# T_STorM32_NT_motor_v42ECg4_001.net
KiCad netlist of a schematic drawn in EAGLE
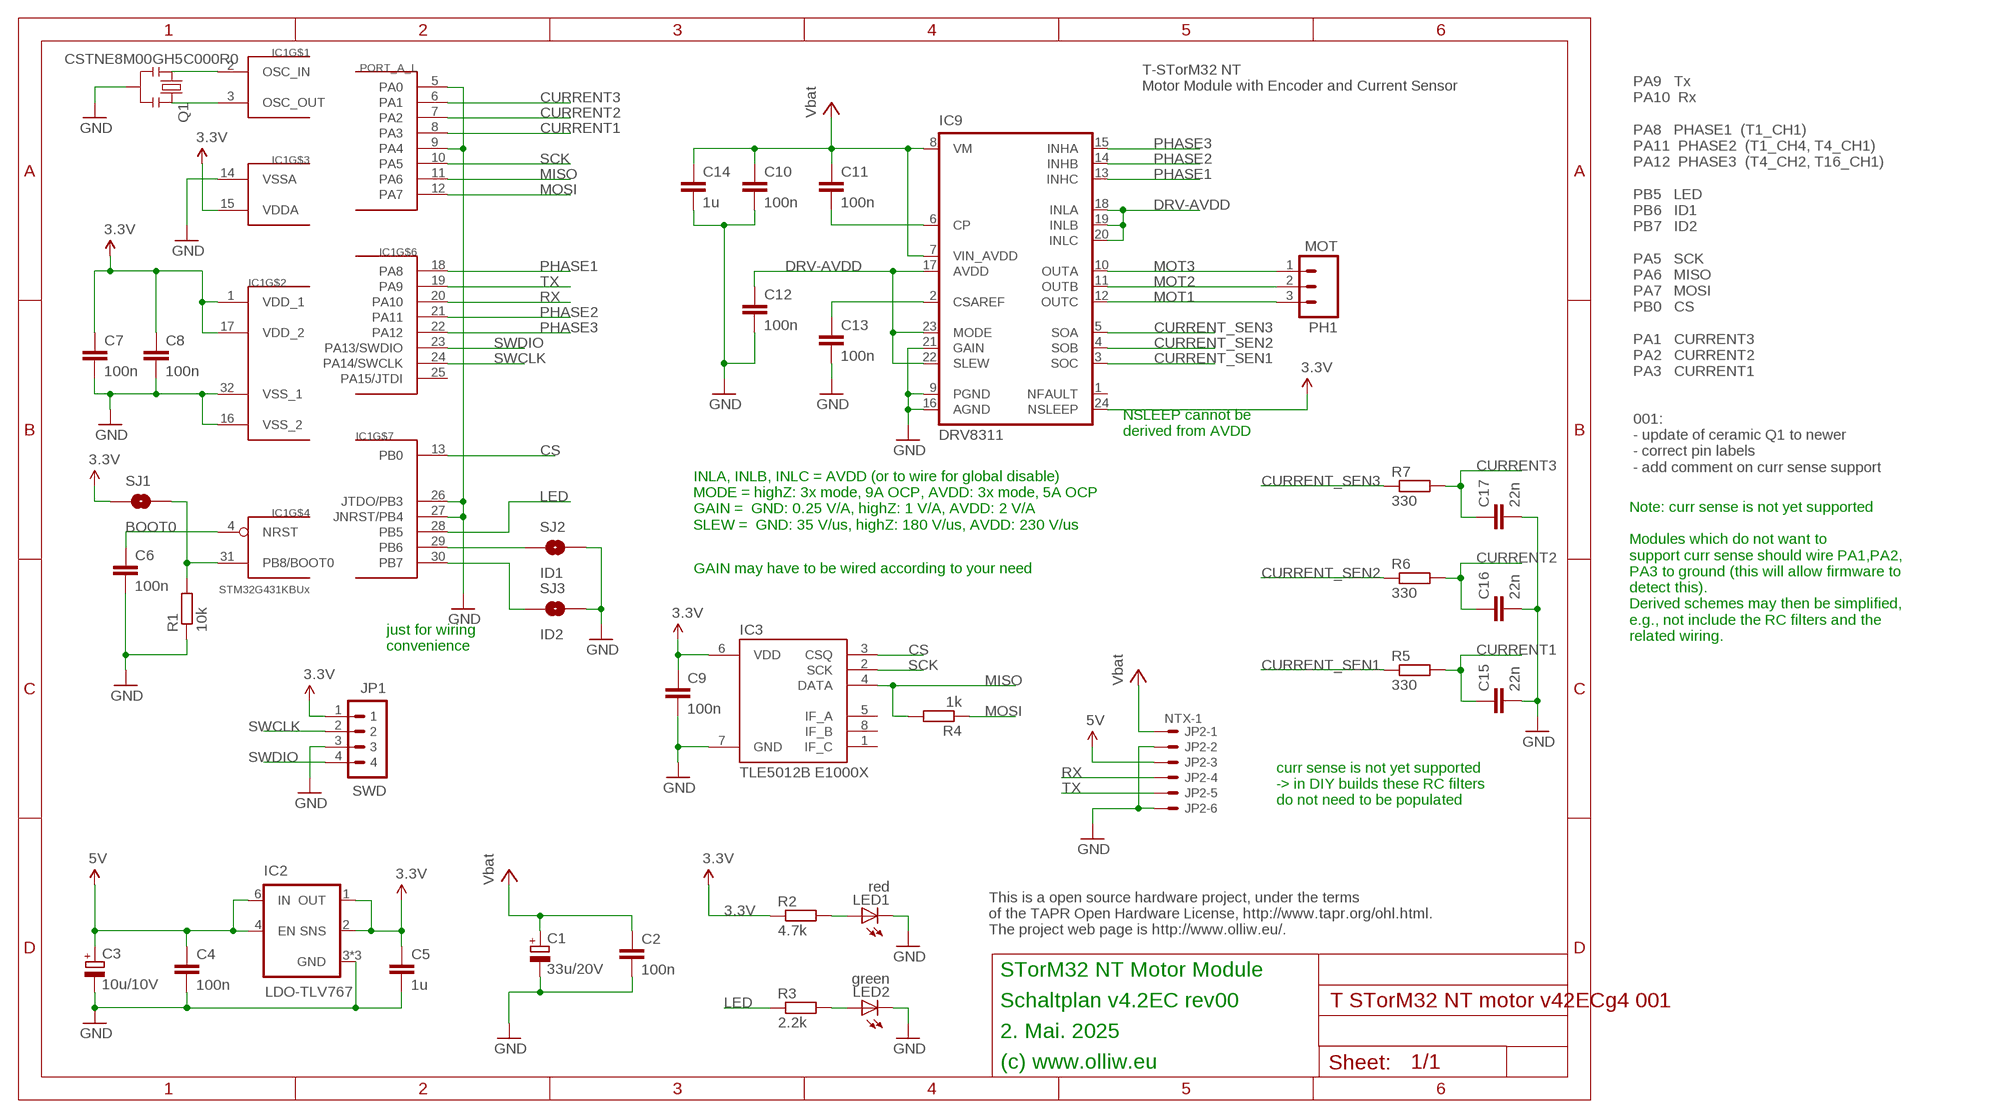
[diagram p0: schematic, sheet 1]

(export (version "E")
  (design (tool "Eeschema 10.0.6"))
  (components
    (comp (ref "C1")
      (value "33u/20V")
      (footprint "eagle-import:SMC_C")
      (libsource (lib "eagle-import") (part "CPOL-EUSMCC"))
    )
    (comp (ref "C2")
      (value "100n")
      (footprint "eagle-import:C0603")
      (libsource (lib "eagle-import") (part "C-EUC0603"))
    )
    (comp (ref "C3")
      (value "10u/10V")
      (footprint "eagle-import:SMC_B")
      (libsource (lib "eagle-import") (part "CPOL-EUSMCB"))
    )
    (comp (ref "C4")
      (value "100n")
      (footprint "eagle-import:C0603")
      (libsource (lib "eagle-import") (part "C-EUC0603"))
    )
    (comp (ref "C5")
      (value "1u")
      (footprint "eagle-import:C0603")
      (libsource (lib "eagle-import") (part "C-EUC0603"))
    )
    (comp (ref "C6")
      (value "100n")
      (footprint "eagle-import:C0402")
      (libsource (lib "eagle-import") (part "C-EUC0402"))
    )
    (comp (ref "C7")
      (value "100n")
      (footprint "eagle-import:C0402")
      (libsource (lib "eagle-import") (part "C-EUC0402"))
    )
    (comp (ref "C8")
      (value "100n")
      (footprint "eagle-import:C0402")
      (libsource (lib "eagle-import") (part "C-EUC0402"))
    )
    (comp (ref "C9")
      (value "100n")
      (footprint "eagle-import:C0402")
      (libsource (lib "eagle-import") (part "C-EUC0402"))
    )
    (comp (ref "C10")
      (value "100n")
      (footprint "eagle-import:C0402")
      (libsource (lib "eagle-import") (part "C-EUC0402"))
    )
    (comp (ref "C11")
      (value "100n")
      (footprint "eagle-import:C0402")
      (libsource (lib "eagle-import") (part "C-EUC0402"))
    )
    (comp (ref "C12")
      (value "100n")
      (footprint "eagle-import:C0402")
      (libsource (lib "eagle-import") (part "C-EUC0402"))
    )
    (comp (ref "C13")
      (value "100n")
      (footprint "eagle-import:C0402")
      (libsource (lib "eagle-import") (part "C-EUC0402"))
    )
    (comp (ref "C14")
      (value "1u")
      (footprint "eagle-import:C0603")
      (libsource (lib "eagle-import") (part "C-EUC0603"))
    )
    (comp (ref "C15")
      (value "22n")
      (footprint "eagle-import:C0402")
      (libsource (lib "eagle-import") (part "C-EUC0402"))
    )
    (comp (ref "C16")
      (value "22n")
      (footprint "eagle-import:C0402")
      (libsource (lib "eagle-import") (part "C-EUC0402"))
    )
    (comp (ref "C17")
      (value "22n")
      (footprint "eagle-import:C0402")
      (libsource (lib "eagle-import") (part "C-EUC0402"))
    )
    (comp (ref "IC1")
      (value "STM32G431KBUx")
      (footprint "eagle-import:UFQFPN32")
      (libsource (lib "eagle-import") (part "STM32G4X1KX"))
    )
    (comp (ref "IC2")
      (value "LDO-TLV767")
      (footprint "eagle-import:WSON-6-2X2")
      (libsource (lib "eagle-import") (part "LDO-TLV767"))
    )
    (comp (ref "IC3")
      (value "TLE5012B E1000X")
      (footprint "eagle-import:SO08")
      (libsource (lib "eagle-import") (part "TLE5012B"))
    )
    (comp (ref "IC9")
      (value "DRV8311")
      (footprint "eagle-import:QFN(WQFN)24-3X3-DRV8311")
      (libsource (lib "eagle-import") (part "DRV8311"))
    )
    (comp (ref "JP1")
      (value "SWD")
      (footprint "eagle-import:4X1_1P27_OCT_BILEX")
      (libsource (lib "eagle-import") (part "P4X1_1P27-OCT_BILEX"))
    )
    (comp (ref "JP2")
      (value "NTX-1")
      (footprint "eagle-import:SM06B-SRSS-TB")
      (libsource (lib "eagle-import") (part "?M06B-SRSS-TBS"))
    )
    (comp (ref "LED1")
      (value "red")
      (footprint "eagle-import:CHIPLED_0603")
      (libsource (lib "eagle-import") (part "LEDCHIPLED_0603"))
    )
    (comp (ref "LED2")
      (value "green")
      (footprint "eagle-import:CHIPLED_0603")
      (libsource (lib "eagle-import") (part "LEDCHIPLED_0603"))
    )
    (comp (ref "PH1")
      (value "MOT")
      (footprint "eagle-import:1X03_NO_SILK")
      (libsource (lib "eagle-import") (part "M031X03_NO_SILK"))
    )
    (comp (ref "Q1")
      (value "CSTNE8M00GH5C000R0")
      (footprint "eagle-import:RESONATOR-SMD")
      (libsource (lib "eagle-import") (part "RESONATORSMD"))
    )
    (comp (ref "R1")
      (value "10k")
      (footprint "eagle-import:R0402")
      (libsource (lib "eagle-import") (part "R-EU_R0402"))
    )
    (comp (ref "R2")
      (value "4.7k")
      (footprint "eagle-import:R0402")
      (libsource (lib "eagle-import") (part "R-EU_R0402"))
    )
    (comp (ref "R3")
      (value "2.2k")
      (footprint "eagle-import:R0402")
      (libsource (lib "eagle-import") (part "R-EU_R0402"))
    )
    (comp (ref "R4")
      (value "1k")
      (footprint "eagle-import:R0402")
      (libsource (lib "eagle-import") (part "R-EU_R0402"))
    )
    (comp (ref "R5")
      (value "330")
      (footprint "eagle-import:R0402")
      (libsource (lib "eagle-import") (part "R-EU_R0402"))
    )
    (comp (ref "R6")
      (value "330")
      (footprint "eagle-import:R0402")
      (libsource (lib "eagle-import") (part "R-EU_R0402"))
    )
    (comp (ref "R7")
      (value "330")
      (footprint "eagle-import:R0402")
      (libsource (lib "eagle-import") (part "R-EU_R0402"))
    )
    (comp (ref "SJ1")
      (value "BOOT0")
      (footprint "eagle-import:SJ_2S-NO")
      (libsource (lib "eagle-import") (part "SOLDERJUMPERNO"))
    )
    (comp (ref "SJ2")
      (value "ID1")
      (footprint "eagle-import:SJ_2S-NO")
      (libsource (lib "eagle-import") (part "SOLDERJUMPERNO"))
    )
    (comp (ref "SJ3")
      (value "ID2")
      (footprint "eagle-import:SJ_2S-NO")
      (libsource (lib "eagle-import") (part "SOLDERJUMPERNO"))
    )
  )
  (nets
    (net (code "1") (name "/CS") (class "Default")
      (node (ref "IC1") (pin "13") (pinfunction "PB0_13") (pintype "bidirectional"))
      (node (ref "IC3") (pin "3") (pinfunction "CSQ_3") (pintype "input"))
    )
    (net (code "2") (name "/CURRENT1") (class "Default")
      (node (ref "C15") (pin "1") (pinfunction "1_1") (pintype "passive"))
      (node (ref "IC1") (pin "8") (pinfunction "PA3_8") (pintype "bidirectional"))
      (node (ref "R5") (pin "2") (pinfunction "2_2") (pintype "passive"))
    )
    (net (code "3") (name "/CURRENT2") (class "Default")
      (node (ref "C16") (pin "1") (pinfunction "1_1") (pintype "passive"))
      (node (ref "IC1") (pin "7") (pinfunction "PA2_7") (pintype "bidirectional"))
      (node (ref "R6") (pin "2") (pinfunction "2_2") (pintype "passive"))
    )
    (net (code "4") (name "/CURRENT3") (class "Default")
      (node (ref "C17") (pin "1") (pinfunction "1_1") (pintype "passive"))
      (node (ref "IC1") (pin "6") (pinfunction "PA1_6") (pintype "bidirectional"))
      (node (ref "R7") (pin "2") (pinfunction "2_2") (pintype "passive"))
    )
    (net (code "5") (name "/CURRENT_SEN1") (class "Default")
      (node (ref "IC9") (pin "3") (pinfunction "SOC_3") (pintype "output"))
      (node (ref "R5") (pin "1") (pinfunction "1_1") (pintype "passive"))
    )
    (net (code "6") (name "/CURRENT_SEN2") (class "Default")
      (node (ref "IC9") (pin "4") (pinfunction "SOB_4") (pintype "output"))
      (node (ref "R6") (pin "1") (pinfunction "1_1") (pintype "passive"))
    )
    (net (code "7") (name "/CURRENT_SEN3") (class "Default")
      (node (ref "IC9") (pin "5") (pinfunction "SOA_5") (pintype "output"))
      (node (ref "R7") (pin "1") (pinfunction "1_1") (pintype "passive"))
    )
    (net (code "8") (name "/DRV-AVDD") (class "Default")
      (node (ref "C12") (pin "1") (pinfunction "1_1") (pintype "passive"))
      (node (ref "IC9") (pin "17") (pinfunction "AVDD_17") (pintype "power_in"))
      (node (ref "IC9") (pin "18") (pinfunction "INLA_18") (pintype "input"))
      (node (ref "IC9") (pin "19") (pinfunction "INLB_19") (pintype "input"))
      (node (ref "IC9") (pin "20") (pinfunction "INLC_20") (pintype "input"))
      (node (ref "IC9") (pin "22") (pinfunction "SLEW_22") (pintype "input"))
      (node (ref "IC9") (pin "23") (pinfunction "MODE_23") (pintype "input"))
    )
    (net (code "9") (name "/LED") (class "Default")
      (node (ref "IC1") (pin "28") (pinfunction "PB5_28") (pintype "bidirectional"))
      (node (ref "R3") (pin "1") (pinfunction "1_1") (pintype "passive"))
    )
    (net (code "10") (name "/MISO") (class "Default")
      (node (ref "IC1") (pin "11") (pinfunction "PA6_11") (pintype "bidirectional"))
      (node (ref "IC3") (pin "4") (pinfunction "DATA_4") (pintype "bidirectional"))
      (node (ref "R4") (pin "2") (pinfunction "2_2") (pintype "passive"))
    )
    (net (code "11") (name "/MOSI") (class "Default")
      (node (ref "IC1") (pin "12") (pinfunction "PA7_12") (pintype "bidirectional"))
      (node (ref "R4") (pin "1") (pinfunction "1_1") (pintype "passive"))
    )
    (net (code "12") (name "/MOT1") (class "Default")
      (node (ref "IC9") (pin "12") (pinfunction "OUTC_12") (pintype "output"))
      (node (ref "PH1") (pin "3") (pinfunction "3_3") (pintype "passive"))
    )
    (net (code "13") (name "/MOT2") (class "Default")
      (node (ref "IC9") (pin "11") (pinfunction "OUTB_11") (pintype "output"))
      (node (ref "PH1") (pin "2") (pinfunction "2_2") (pintype "passive"))
    )
    (net (code "14") (name "/MOT3") (class "Default")
      (node (ref "IC9") (pin "10") (pinfunction "OUTA_10") (pintype "output"))
      (node (ref "PH1") (pin "1") (pinfunction "1_1") (pintype "passive"))
    )
    (net (code "15") (name "/PHASE1") (class "Default")
      (node (ref "IC1") (pin "18") (pinfunction "PA8_18") (pintype "bidirectional"))
      (node (ref "IC9") (pin "13") (pinfunction "INHC_13") (pintype "input"))
    )
    (net (code "16") (name "/PHASE2") (class "Default")
      (node (ref "IC1") (pin "21") (pinfunction "PA11_21") (pintype "bidirectional"))
      (node (ref "IC9") (pin "14") (pinfunction "INHB_14") (pintype "input"))
    )
    (net (code "17") (name "/PHASE3") (class "Default")
      (node (ref "IC1") (pin "22") (pinfunction "PA12_22") (pintype "bidirectional"))
      (node (ref "IC9") (pin "15") (pinfunction "INHA_15") (pintype "input"))
    )
    (net (code "18") (name "/RX") (class "Default")
      (node (ref "IC1") (pin "20") (pinfunction "PA10_20") (pintype "bidirectional"))
      (node (ref "JP2") (pin "4") (pinfunction "S_4") (pintype "passive"))
    )
    (net (code "19") (name "/SCK") (class "Default")
      (node (ref "IC1") (pin "10") (pinfunction "PA5_10") (pintype "bidirectional"))
      (node (ref "IC3") (pin "2") (pinfunction "SCK_2") (pintype "input"))
    )
    (net (code "20") (name "/SWCLK") (class "Default")
      (node (ref "IC1") (pin "24") (pinfunction "PA14/SWCLK_24") (pintype "bidirectional"))
      (node (ref "JP1") (pin "2") (pinfunction "2_2") (pintype "passive"))
    )
    (net (code "21") (name "/SWDIO") (class "Default")
      (node (ref "IC1") (pin "23") (pinfunction "PA13/SWDIO_23") (pintype "bidirectional"))
      (node (ref "JP1") (pin "4") (pinfunction "4_4") (pintype "passive"))
    )
    (net (code "22") (name "/TX") (class "Default")
      (node (ref "IC1") (pin "19") (pinfunction "PA9_19") (pintype "bidirectional"))
      (node (ref "JP2") (pin "5") (pinfunction "S_5") (pintype "passive"))
    )
    (net (code "23") (name "3.3V") (class "Default")
      (node (ref "C5") (pin "1") (pinfunction "1_1") (pintype "passive"))
      (node (ref "C7") (pin "1") (pinfunction "1_1") (pintype "passive"))
      (node (ref "C8") (pin "1") (pinfunction "1_1") (pintype "passive"))
      (node (ref "C9") (pin "1") (pinfunction "1_1") (pintype "passive"))
      (node (ref "IC1") (pin "1") (pinfunction "VDD_1_1") (pintype "power_in"))
      (node (ref "IC1") (pin "15") (pinfunction "VDDA_15") (pintype "power_in"))
      (node (ref "IC1") (pin "17") (pinfunction "VDD_2_17") (pintype "power_in"))
      (node (ref "IC2") (pin "1") (pinfunction "OUT_1") (pintype "output"))
      (node (ref "IC2") (pin "2") (pinfunction "SNS_2") (pintype "input"))
      (node (ref "IC3") (pin "6") (pinfunction "VDD_6") (pintype "power_in"))
      (node (ref "IC9") (pin "24") (pinfunction "NSLEEP_24") (pintype "input"))
      (node (ref "JP1") (pin "1") (pinfunction "1_1") (pintype "passive"))
      (node (ref "R2") (pin "1") (pinfunction "1_1") (pintype "passive"))
      (node (ref "SJ1") (pin "1") (pinfunction "1_1") (pintype "passive"))
    )
    (net (code "24") (name "5V") (class "Default")
      (node (ref "C3") (pin "+") (pinfunction "+_+") (pintype "passive"))
      (node (ref "C4") (pin "1") (pinfunction "1_1") (pintype "passive"))
      (node (ref "IC2") (pin "4") (pinfunction "EN_4") (pintype "input"))
      (node (ref "IC2") (pin "6") (pinfunction "IN_6") (pintype "power_in"))
      (node (ref "JP2") (pin "3") (pinfunction "S_3") (pintype "passive"))
    )
    (net (code "25") (name "GND") (class "Default")
      (node (ref "C1") (pin "-") (pinfunction "-_-") (pintype "passive"))
      (node (ref "C10") (pin "2") (pinfunction "2_2") (pintype "passive"))
      (node (ref "C12") (pin "2") (pinfunction "2_2") (pintype "passive"))
      (node (ref "C13") (pin "2") (pinfunction "2_2") (pintype "passive"))
      (node (ref "C14") (pin "2") (pinfunction "2_2") (pintype "passive"))
      (node (ref "C15") (pin "2") (pinfunction "2_2") (pintype "passive"))
      (node (ref "C16") (pin "2") (pinfunction "2_2") (pintype "passive"))
      (node (ref "C17") (pin "2") (pinfunction "2_2") (pintype "passive"))
      (node (ref "C2") (pin "2") (pinfunction "2_2") (pintype "passive"))
      (node (ref "C3") (pin "-") (pinfunction "-_-") (pintype "passive"))
      (node (ref "C4") (pin "2") (pinfunction "2_2") (pintype "passive"))
      (node (ref "C5") (pin "2") (pinfunction "2_2") (pintype "passive"))
      (node (ref "C6") (pin "2") (pinfunction "2_2") (pintype "passive"))
      (node (ref "C7") (pin "2") (pinfunction "2_2") (pintype "passive"))
      (node (ref "C8") (pin "2") (pinfunction "2_2") (pintype "passive"))
      (node (ref "C9") (pin "2") (pinfunction "2_2") (pintype "passive"))
      (node (ref "IC1") (pin "14") (pinfunction "VSSA_14") (pintype "power_in"))
      (node (ref "IC1") (pin "16") (pinfunction "VSS_2_16") (pintype "power_in"))
      (node (ref "IC1") (pin "26") (pinfunction "JTDO/PB3_26") (pintype "bidirectional"))
      (node (ref "IC1") (pin "27") (pinfunction "JNRST/PB4_27") (pintype "bidirectional"))
      (node (ref "IC1") (pin "32") (pinfunction "VSS_1_32") (pintype "power_in"))
      (node (ref "IC1") (pin "5") (pinfunction "PA0_5") (pintype "bidirectional"))
      (node (ref "IC1") (pin "9") (pinfunction "PA4_9") (pintype "bidirectional"))
      (node (ref "IC2") (pin "3") (pinfunction "GND_3") (pintype "power_in"))
      (node (ref "IC2") (pin "5") (pinfunction "GND_5") (pintype "power_in"))
      (node (ref "IC2") (pin "7") (pinfunction "GND_7") (pintype "power_in"))
      (node (ref "IC3") (pin "7") (pinfunction "GND_7") (pintype "power_in"))
      (node (ref "IC9") (pin "16") (pinfunction "AGND_16") (pintype "power_in"))
      (node (ref "IC9") (pin "21") (pinfunction "GAIN_21") (pintype "input"))
      (node (ref "IC9") (pin "9") (pinfunction "PGND_9") (pintype "power_in"))
      (node (ref "JP1") (pin "3") (pinfunction "3_3") (pintype "passive"))
      (node (ref "JP2") (pin "2") (pinfunction "S_2") (pintype "passive"))
      (node (ref "JP2") (pin "6") (pinfunction "S_6") (pintype "passive"))
      (node (ref "LED1") (pin "C") (pinfunction "C_C") (pintype "passive"))
      (node (ref "LED2") (pin "C") (pinfunction "C_C") (pintype "passive"))
      (node (ref "Q1") (pin "2") (pinfunction "2_2") (pintype "passive"))
      (node (ref "R1") (pin "1") (pinfunction "1_1") (pintype "passive"))
      (node (ref "SJ2") (pin "2") (pinfunction "2_2") (pintype "passive"))
      (node (ref "SJ3") (pin "2") (pinfunction "2_2") (pintype "passive"))
    )
    (net (code "26") (name "Net-(IC1A-OSC_IN)") (class "Default")
      (node (ref "IC1") (pin "2") (pinfunction "OSC_IN_2") (pintype "input"))
      (node (ref "Q1") (pin "1") (pinfunction "1_1") (pintype "passive"))
    )
    (net (code "27") (name "Net-(IC1A-OSC_OUT)") (class "Default")
      (node (ref "IC1") (pin "3") (pinfunction "OSC_OUT_3") (pintype "output"))
      (node (ref "Q1") (pin "3") (pinfunction "3_3") (pintype "passive"))
    )
    (net (code "28") (name "Net-(IC1D-NRST)") (class "Default")
      (node (ref "C6") (pin "1") (pinfunction "1_1") (pintype "passive"))
      (node (ref "IC1") (pin "4") (pinfunction "NRST_4") (pintype "input"))
    )
    (net (code "29") (name "Net-(IC1D-PB8{slash}BOOT0)") (class "Default")
      (node (ref "IC1") (pin "31") (pinfunction "PB8/BOOT0_31") (pintype "input"))
      (node (ref "R1") (pin "2") (pinfunction "2_2") (pintype "passive"))
      (node (ref "SJ1") (pin "2") (pinfunction "2_2") (pintype "passive"))
    )
    (net (code "30") (name "Net-(IC1G-PB6)") (class "Default")
      (node (ref "IC1") (pin "29") (pinfunction "PB6_29") (pintype "bidirectional"))
      (node (ref "SJ2") (pin "1") (pinfunction "1_1") (pintype "passive"))
    )
    (net (code "31") (name "Net-(IC1G-PB7)") (class "Default")
      (node (ref "IC1") (pin "30") (pinfunction "PB7_30") (pintype "bidirectional"))
      (node (ref "SJ3") (pin "1") (pinfunction "1_1") (pintype "passive"))
    )
    (net (code "32") (name "Net-(IC9-CP)") (class "Default")
      (node (ref "C11") (pin "2") (pinfunction "2_2") (pintype "passive"))
      (node (ref "IC9") (pin "6") (pinfunction "CP_6") (pintype "power_in"))
    )
    (net (code "33") (name "Net-(IC9-CSAREF)") (class "Default")
      (node (ref "C13") (pin "1") (pinfunction "1_1") (pintype "passive"))
      (node (ref "IC9") (pin "2") (pinfunction "CSAREF_2") (pintype "power_in"))
    )
    (net (code "34") (name "Net-(LED1-PadA)") (class "Default")
      (node (ref "LED1") (pin "A") (pinfunction "A_A") (pintype "passive"))
      (node (ref "R2") (pin "2") (pinfunction "2_2") (pintype "passive"))
    )
    (net (code "35") (name "Net-(LED2-PadA)") (class "Default")
      (node (ref "LED2") (pin "A") (pinfunction "A_A") (pintype "passive"))
      (node (ref "R3") (pin "2") (pinfunction "2_2") (pintype "passive"))
    )
    (net (code "36") (name "Vbat") (class "Default")
      (node (ref "C1") (pin "+") (pinfunction "+_+") (pintype "passive"))
      (node (ref "C10") (pin "1") (pinfunction "1_1") (pintype "passive"))
      (node (ref "C11") (pin "1") (pinfunction "1_1") (pintype "passive"))
      (node (ref "C14") (pin "1") (pinfunction "1_1") (pintype "passive"))
      (node (ref "C2") (pin "1") (pinfunction "1_1") (pintype "passive"))
      (node (ref "IC9") (pin "7") (pinfunction "VIN_AVDD_7") (pintype "power_in"))
      (node (ref "IC9") (pin "8") (pinfunction "VM_8") (pintype "power_in"))
      (node (ref "JP2") (pin "1") (pinfunction "S_1") (pintype "passive"))
    )
    (net (code "37") (name "unconnected-(IC1F-PA15{slash}JTDI-Pad25)") (class "Default")
      (node (ref "IC1") (pin "25") (pinfunction "PA15/JTDI_25") (pintype "bidirectional"))
    )
    (net (code "38") (name "unconnected-(IC3-IF_A-Pad5)") (class "Default")
      (node (ref "IC3") (pin "5") (pinfunction "IF_A_5") (pintype "bidirectional"))
    )
    (net (code "39") (name "unconnected-(IC3-IF_B-Pad8)") (class "Default")
      (node (ref "IC3") (pin "8") (pinfunction "IF_B_8") (pintype "output"))
    )
    (net (code "40") (name "unconnected-(IC3-IF_C-Pad1)") (class "Default")
      (node (ref "IC3") (pin "1") (pinfunction "IF_C_1") (pintype "bidirectional"))
    )
    (net (code "41") (name "unconnected-(IC9-NFAULT-Pad1)") (class "Default")
      (node (ref "IC9") (pin "1") (pinfunction "NFAULT_1") (pintype "output"))
    )
  )
)
